# PAGE2.net
KiCad netlist of a schematic drawn in Altium Designer
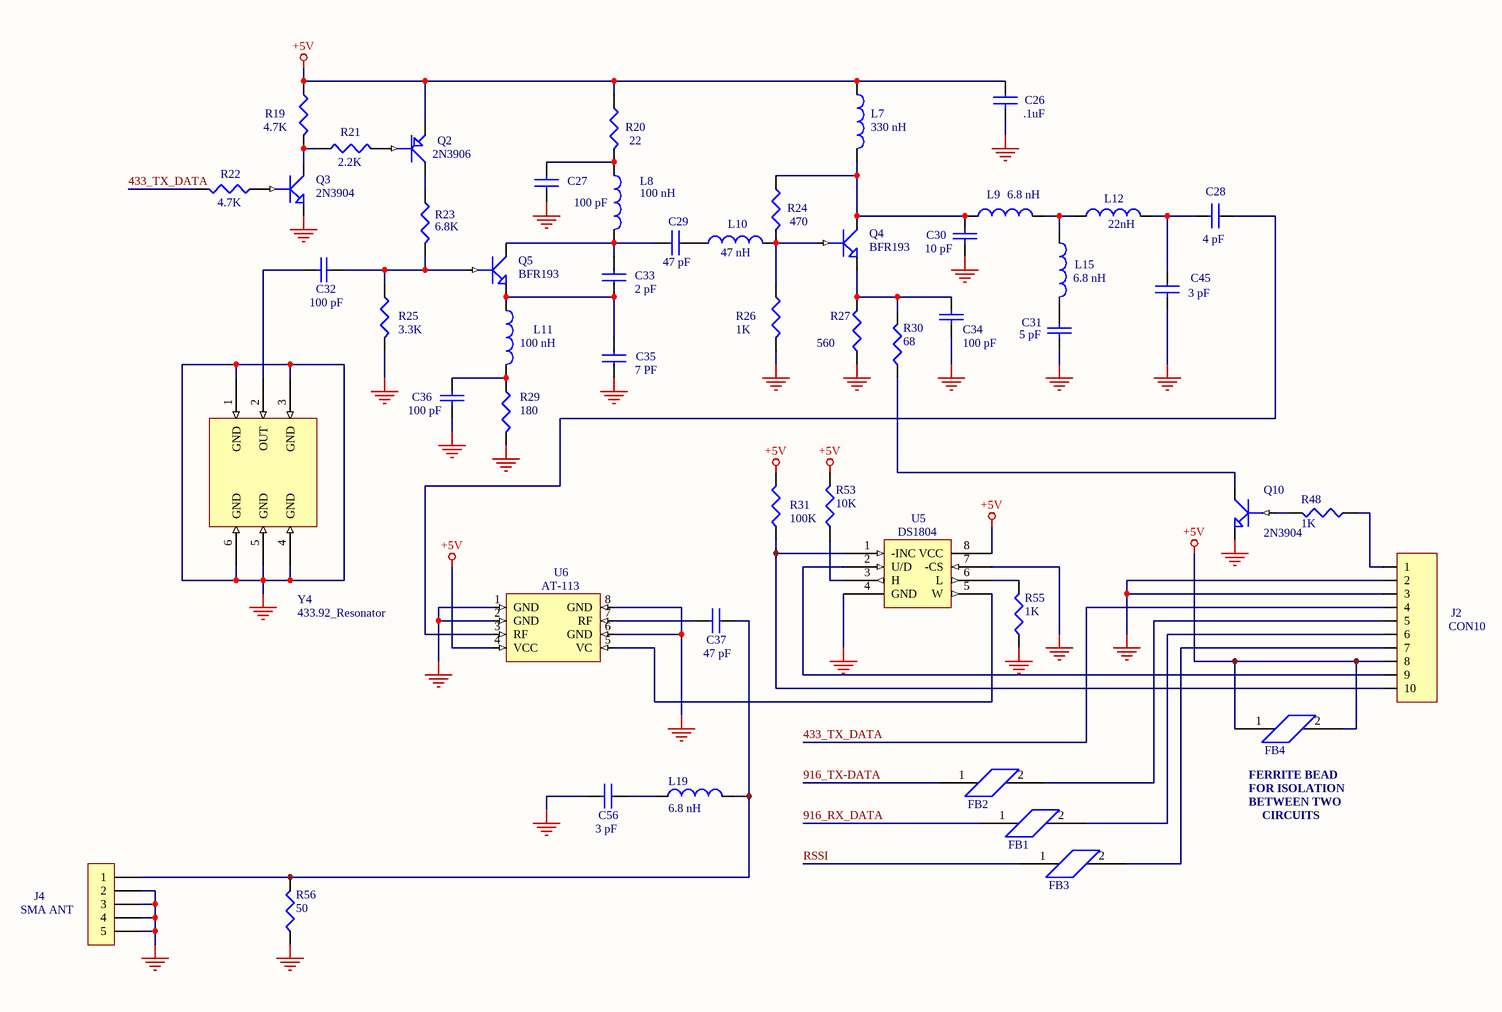
[diagram p0: PAGE2.SCHDOC]

(export (version "E")
  (design (tool "Eeschema 10.0.6"))
  (components
    (comp (ref "C26") (value ".1uF") (footprint "0603") (libsource (lib "*") (part "CAP_NP")))
    (comp (ref "C27") (value "100 pF") (footprint "0603") (libsource (lib "*") (part "CAP_NP")))
    (comp (ref "C28") (value "4 pF") (footprint "0603") (libsource (lib "*") (part "CAP_NP")))
    (comp (ref "C29") (value "47 pF") (footprint "0603") (libsource (lib "*") (part "CAP_NP")))
    (comp (ref "C30")
      (value "10 pF")
      (footprint "0603")
      (description "Capacitor")
      (libsource (lib "*") (part "CAP"))
    )
    (comp (ref "C31")
      (value "5 pF")
      (footprint "0603")
      (description "Capacitor")
      (libsource (lib "*") (part "CAP"))
    )
    (comp (ref "C32")
      (value "100 pF")
      (footprint "0603")
      (description "Capacitor")
      (libsource (lib "*") (part "CAP"))
    )
    (comp (ref "C33") (value "2 pF") (footprint "0603") (libsource (lib "*") (part "CAP_NP")))
    (comp (ref "C34")
      (value "100 pF")
      (footprint "0603")
      (description "Capacitor")
      (libsource (lib "*") (part "CAP"))
    )
    (comp (ref "C35") (value "7 PF") (footprint "0603") (libsource (lib "*") (part "CAP_NP")))
    (comp (ref "C36")
      (value "100 pF")
      (footprint "0603")
      (description "Capacitor")
      (libsource (lib "*") (part "CAP"))
    )
    (comp (ref "C37") (value "47 pF") (footprint "0603") (libsource (lib "*") (part "CAP_NP")))
    (comp (ref "C45") (value "3 pF") (footprint "0603") (libsource (lib "*") (part "CAP_NP")))
    (comp (ref "C56") (value "3 pF") (footprint "0603") (libsource (lib "*") (part "CAP_NP")))
    (comp (ref "FB1") (value "FB") (footprint "0603") (libsource (lib "*") (part "FB_0603")))
    (comp (ref "FB2") (value "FB") (footprint "0603") (libsource (lib "*") (part "FB_0603")))
    (comp (ref "FB3") (value "FB") (footprint "0603") (libsource (lib "*") (part "FB_0603")))
    (comp (ref "FB4") (value "FB") (footprint "0603") (libsource (lib "*") (part "FB_0603")))
    (comp (ref "J2") (value "CON10") (footprint "1X10 HEADER") (libsource (lib "*") (part "CON10")))
    (comp (ref "J4")
      (value "SMA ANT")
      (footprint "50 OHM ANT")
      (description "Connector")
      (libsource (lib "*") (part "CON5"))
    )
    (comp (ref "L7") (value "330 nH") (footprint "0805") (libsource (lib "*") (part "INDUCTOR")))
    (comp (ref "L8") (value "100 nH") (footprint "0603") (libsource (lib "*") (part "INDUCTOR")))
    (comp (ref "L9") (value "6.8 nH") (footprint "0603") (libsource (lib "*") (part "INDUCTOR")))
    (comp (ref "L10") (value "47 nH") (footprint "0603") (libsource (lib "*") (part "INDUCTOR")))
    (comp (ref "L11") (value "100 nH") (footprint "0603") (libsource (lib "*") (part "INDUCTOR")))
    (comp (ref "L12") (value "22nH") (footprint "0603") (libsource (lib "*") (part "INDUCTOR")))
    (comp (ref "L15") (value "6.8 nH") (footprint "0603") (libsource (lib "*") (part "INDUCTOR")))
    (comp (ref "L19") (value "6.8 nH") (footprint "0603") (libsource (lib "*") (part "INDUCTOR")))
    (comp (ref "Q2")
      (value "2N3906")
      (footprint "SOT23 TRANS")
      (description "PNP Transistor")
      (libsource (lib "*") (part "PNP1"))
    )
    (comp (ref "Q3")
      (value "2N3904")
      (footprint "SOT23 TRANS")
      (description "NPN Transistor")
      (libsource (lib "*") (part "NPN1"))
    )
    (comp (ref "Q4")
      (value "BFR193")
      (footprint "SOT23 TRANS")
      (description "NPN Transistor")
      (libsource (lib "*") (part "NPN1"))
    )
    (comp (ref "Q5")
      (value "BFR193")
      (footprint "SOT23 TRANS")
      (description "NPN Transistor")
      (libsource (lib "*") (part "NPN1"))
    )
    (comp (ref "Q10")
      (value "2N3904")
      (footprint "SOT23 TRANS")
      (description "NPN Transistor")
      (libsource (lib "*") (part "NPN1"))
    )
    (comp (ref "R19") (value "4.7K") (footprint "0603") (libsource (lib "*") (part "RESISTOR")))
    (comp (ref "R20") (value "22") (footprint "0603") (libsource (lib "*") (part "RESISTOR")))
    (comp (ref "R21") (value "2.2K") (footprint "0603") (libsource (lib "*") (part "RESISTOR")))
    (comp (ref "R22") (value "4.7K") (footprint "0603") (libsource (lib "*") (part "RESISTOR")))
    (comp (ref "R23") (value "6.8K") (footprint "0603") (libsource (lib "*") (part "RESISTOR")))
    (comp (ref "R24") (value "470") (footprint "0603") (libsource (lib "*") (part "RESISTOR")))
    (comp (ref "R25") (value "3.3K") (footprint "0603") (libsource (lib "*") (part "RESISTOR")))
    (comp (ref "R26") (value "1K") (footprint "0603") (libsource (lib "*") (part "RESISTOR")))
    (comp (ref "R27") (value "560") (footprint "0603") (libsource (lib "*") (part "RESISTOR")))
    (comp (ref "R29") (value "180") (footprint "0603") (libsource (lib "*") (part "RESISTOR")))
    (comp (ref "R30") (value "68") (footprint "0603") (libsource (lib "*") (part "RESISTOR")))
    (comp (ref "R31") (value "100K") (footprint "0603") (libsource (lib "*") (part "RESISTOR")))
    (comp (ref "R48") (value "1K") (footprint "0603") (libsource (lib "*") (part "RESISTOR")))
    (comp (ref "R53") (value "10K") (footprint "0603") (libsource (lib "*") (part "RESISTOR")))
    (comp (ref "R55") (value "1K") (footprint "0603") (libsource (lib "*") (part "RESISTOR")))
    (comp (ref "R56") (value "50") (footprint "0603") (libsource (lib "*") (part "RESISTOR")))
    (comp (ref "U5") (value "DS1804") (footprint "SO8 SMALL") (libsource (lib "*") (part "DS1804")))
    (comp (ref "U6") (value "AT-113") (footprint "SO8") (libsource (lib "*") (part "AT-113A")))
    (comp (ref "Y4")
      (value "433.92_Resonator")
      (footprint "RESONATOR2")
      (libsource (lib "*") (part "RESONATOR2"))
    )
  )
  (nets
    (net (code "1") (name "+5V") (class "Default")
      (node (ref "C26") (pin "1") (pinfunction "1_1") (pintype "passive"))
      (node (ref "FB4") (pin "1") (pinfunction "2_1") (pintype "passive"))
      (node (ref "FB4") (pin "2") (pinfunction "1_2") (pintype "passive"))
      (node (ref "J2") (pin "8") (pinfunction "8_8") (pintype "passive"))
      (node (ref "L7") (pin "1") (pinfunction "1_1") (pintype "passive"))
      (node (ref "Q2") (pin "E") (pinfunction "E_E") (pintype "passive"))
      (node (ref "R19") (pin "1") (pinfunction "1_1") (pintype "passive"))
      (node (ref "R20") (pin "1") (pinfunction "1_1") (pintype "passive"))
      (node (ref "R31") (pin "1") (pinfunction "1_1") (pintype "passive"))
      (node (ref "R53") (pin "2") (pinfunction "2_2") (pintype "passive"))
      (node (ref "U5") (pin "8") (pinfunction "VCC_8") (pintype "power_in"))
      (node (ref "U6") (pin "4") (pinfunction "VCC_4") (pintype "input"))
    )
    (net (code "2") (name "/433_TX_DATA") (class "Default")
      (node (ref "J2") (pin "4") (pinfunction "4_4") (pintype "passive"))
      (node (ref "R22") (pin "2") (pinfunction "2_2") (pintype "passive"))
    )
    (net (code "3") (name "/916_RX_DATA") (class "Default")
      (node (ref "FB1") (pin "1") (pinfunction "2_1") (pintype "passive"))
    )
    (net (code "4") (name "/916_TX-DATA") (class "Default")
      (node (ref "FB2") (pin "1") (pinfunction "2_1") (pintype "passive"))
    )
    (net (code "5") (name "/RSSI") (class "Default")
      (node (ref "FB3") (pin "1") (pinfunction "2_1") (pintype "passive"))
    )
    (net (code "6") (name "GND_SIGNAL") (class "Default")
      (node (ref "C26") (pin "2") (pinfunction "2_2") (pintype "passive"))
      (node (ref "C27") (pin "1") (pinfunction "1_1") (pintype "passive"))
      (node (ref "C30") (pin "2") (pinfunction "2_2") (pintype "passive"))
      (node (ref "C31") (pin "2") (pinfunction "2_2") (pintype "passive"))
      (node (ref "C34") (pin "2") (pinfunction "2_2") (pintype "passive"))
      (node (ref "C35") (pin "1") (pinfunction "1_1") (pintype "passive"))
      (node (ref "C36") (pin "2") (pinfunction "2_2") (pintype "passive"))
      (node (ref "C45") (pin "2") (pinfunction "2_2") (pintype "passive"))
      (node (ref "C56") (pin "2") (pinfunction "2_2") (pintype "passive"))
      (node (ref "J2") (pin "2") (pinfunction "2_2") (pintype "passive"))
      (node (ref "J2") (pin "3") (pinfunction "3_3") (pintype "passive"))
      (node (ref "J4") (pin "2") (pinfunction "2_2") (pintype "passive"))
      (node (ref "J4") (pin "3") (pinfunction "3_3") (pintype "passive"))
      (node (ref "J4") (pin "4") (pinfunction "4_4") (pintype "passive"))
      (node (ref "J4") (pin "5") (pinfunction "5_5") (pintype "passive"))
      (node (ref "Q10") (pin "E") (pinfunction "E_E") (pintype "passive"))
      (node (ref "Q3") (pin "E") (pinfunction "E_E") (pintype "passive"))
      (node (ref "R25") (pin "2") (pinfunction "2_2") (pintype "passive"))
      (node (ref "R26") (pin "2") (pinfunction "2_2") (pintype "passive"))
      (node (ref "R27") (pin "2") (pinfunction "2_2") (pintype "passive"))
      (node (ref "R29") (pin "2") (pinfunction "2_2") (pintype "passive"))
      (node (ref "R55") (pin "1") (pinfunction "1_1") (pintype "passive"))
      (node (ref "R56") (pin "1") (pinfunction "1_1") (pintype "passive"))
      (node (ref "U5") (pin "4") (pinfunction "GND_4") (pintype "power_in"))
      (node (ref "U5") (pin "7") (pinfunction "-CS_7") (pintype "input"))
      (node (ref "U6") (pin "1") (pinfunction "GND_1") (pintype "input"))
      (node (ref "U6") (pin "2") (pinfunction "GND_2") (pintype "input"))
      (node (ref "U6") (pin "6") (pinfunction "GND_6") (pintype "input"))
      (node (ref "U6") (pin "8") (pinfunction "GND_8") (pintype "input"))
      (node (ref "Y4") (pin "1") (pinfunction "GND_1") (pintype "input"))
      (node (ref "Y4") (pin "3") (pinfunction "GND_3") (pintype "input"))
      (node (ref "Y4") (pin "4") (pinfunction "GND_4") (pintype "input"))
      (node (ref "Y4") (pin "5") (pinfunction "GND_5") (pintype "input"))
      (node (ref "Y4") (pin "6") (pinfunction "GND_6") (pintype "input"))
    )
    (net (code "7") (name "Net-(C27-Pad2)") (class "Default")
      (node (ref "C27") (pin "2") (pinfunction "2_2") (pintype "passive"))
      (node (ref "L8") (pin "1") (pinfunction "1_1") (pintype "passive"))
      (node (ref "R20") (pin "2") (pinfunction "2_2") (pintype "passive"))
    )
    (net (code "8") (name "Net-(C28-Pad1)") (class "Default")
      (node (ref "C28") (pin "1") (pinfunction "1_1") (pintype "passive"))
      (node (ref "U6") (pin "3") (pinfunction "RF_3") (pintype "input"))
    )
    (net (code "9") (name "Net-(C28-Pad2)") (class "Default")
      (node (ref "C28") (pin "2") (pinfunction "2_2") (pintype "passive"))
      (node (ref "C45") (pin "1") (pinfunction "1_1") (pintype "passive"))
      (node (ref "L12") (pin "2") (pinfunction "2_2") (pintype "passive"))
    )
    (net (code "10") (name "Net-(C29-Pad1)") (class "Default")
      (node (ref "C29") (pin "1") (pinfunction "1_1") (pintype "passive"))
      (node (ref "L10") (pin "1") (pinfunction "1_1") (pintype "passive"))
    )
    (net (code "11") (name "Net-(C29-Pad2)") (class "Default")
      (node (ref "C29") (pin "2") (pinfunction "2_2") (pintype "passive"))
      (node (ref "C33") (pin "2") (pinfunction "2_2") (pintype "passive"))
      (node (ref "L8") (pin "2") (pinfunction "2_2") (pintype "passive"))
      (node (ref "Q5") (pin "C") (pinfunction "C_C") (pintype "passive"))
    )
    (net (code "12") (name "Net-(C30-Pad1)") (class "Default")
      (node (ref "C30") (pin "1") (pinfunction "1_1") (pintype "passive"))
      (node (ref "L7") (pin "2") (pinfunction "2_2") (pintype "passive"))
      (node (ref "L9") (pin "1") (pinfunction "1_1") (pintype "passive"))
      (node (ref "Q4") (pin "C") (pinfunction "C_C") (pintype "passive"))
      (node (ref "R24") (pin "1") (pinfunction "1_1") (pintype "passive"))
    )
    (net (code "13") (name "Net-(C31-Pad1)") (class "Default")
      (node (ref "C31") (pin "1") (pinfunction "1_1") (pintype "passive"))
      (node (ref "L15") (pin "2") (pinfunction "2_2") (pintype "passive"))
    )
    (net (code "14") (name "Net-(C32-Pad2)") (class "Default")
      (node (ref "C32") (pin "2") (pinfunction "2_2") (pintype "passive"))
      (node (ref "Q5") (pin "B") (pinfunction "B_B") (pintype "input"))
      (node (ref "R23") (pin "2") (pinfunction "2_2") (pintype "passive"))
      (node (ref "R25") (pin "1") (pinfunction "1_1") (pintype "passive"))
    )
    (net (code "15") (name "Net-(C33-Pad1)") (class "Default")
      (node (ref "C33") (pin "1") (pinfunction "1_1") (pintype "passive"))
      (node (ref "C35") (pin "2") (pinfunction "2_2") (pintype "passive"))
      (node (ref "L11") (pin "1") (pinfunction "1_1") (pintype "passive"))
      (node (ref "Q5") (pin "E") (pinfunction "E_E") (pintype "passive"))
    )
    (net (code "16") (name "Net-(C34-Pad1)") (class "Default")
      (node (ref "C34") (pin "1") (pinfunction "1_1") (pintype "passive"))
      (node (ref "Q4") (pin "E") (pinfunction "E_E") (pintype "passive"))
      (node (ref "R27") (pin "1") (pinfunction "1_1") (pintype "passive"))
      (node (ref "R30") (pin "2") (pinfunction "2_2") (pintype "passive"))
    )
    (net (code "17") (name "Net-(C36-Pad1)") (class "Default")
      (node (ref "C36") (pin "1") (pinfunction "1_1") (pintype "passive"))
      (node (ref "L11") (pin "2") (pinfunction "2_2") (pintype "passive"))
      (node (ref "R29") (pin "1") (pinfunction "1_1") (pintype "passive"))
    )
    (net (code "18") (name "Net-(C37-Pad1)") (class "Default")
      (node (ref "C37") (pin "1") (pinfunction "1_1") (pintype "passive"))
      (node (ref "J4") (pin "1") (pinfunction "1_1") (pintype "passive"))
      (node (ref "L19") (pin "2") (pinfunction "2_2") (pintype "passive"))
      (node (ref "R56") (pin "2") (pinfunction "2_2") (pintype "passive"))
    )
    (net (code "19") (name "Net-(C37-Pad2)") (class "Default")
      (node (ref "C37") (pin "2") (pinfunction "2_2") (pintype "passive"))
      (node (ref "U6") (pin "7") (pinfunction "RF_7") (pintype "input"))
    )
    (net (code "20") (name "Net-(C56-Pad1)") (class "Default")
      (node (ref "C56") (pin "1") (pinfunction "1_1") (pintype "passive"))
      (node (ref "L19") (pin "1") (pinfunction "1_1") (pintype "passive"))
    )
    (net (code "21") (name "Net-(FB1-1)") (class "Default")
      (node (ref "FB1") (pin "2") (pinfunction "1_2") (pintype "passive"))
      (node (ref "J2") (pin "6") (pinfunction "6_6") (pintype "passive"))
    )
    (net (code "22") (name "Net-(FB2-1)") (class "Default")
      (node (ref "FB2") (pin "2") (pinfunction "1_2") (pintype "passive"))
      (node (ref "J2") (pin "5") (pinfunction "5_5") (pintype "passive"))
    )
    (net (code "23") (name "Net-(FB3-1)") (class "Default")
      (node (ref "FB3") (pin "2") (pinfunction "1_2") (pintype "passive"))
      (node (ref "J2") (pin "7") (pinfunction "7_7") (pintype "passive"))
    )
    (net (code "24") (name "Net-(J2-Pad1)") (class "Default")
      (node (ref "J2") (pin "1") (pinfunction "1_1") (pintype "passive"))
      (node (ref "R48") (pin "2") (pinfunction "2_2") (pintype "passive"))
    )
    (net (code "25") (name "Net-(L10-Pad2)") (class "Default")
      (node (ref "L10") (pin "2") (pinfunction "2_2") (pintype "passive"))
      (node (ref "Q4") (pin "B") (pinfunction "B_B") (pintype "input"))
      (node (ref "R24") (pin "2") (pinfunction "2_2") (pintype "passive"))
      (node (ref "R26") (pin "1") (pinfunction "1_1") (pintype "passive"))
    )
    (net (code "26") (name "Net-(L12-Pad1)") (class "Default")
      (node (ref "L12") (pin "1") (pinfunction "1_1") (pintype "passive"))
      (node (ref "L15") (pin "1") (pinfunction "1_1") (pintype "passive"))
      (node (ref "L9") (pin "2") (pinfunction "2_2") (pintype "passive"))
    )
    (net (code "27") (name "Net-(Q2-PadB)") (class "Default")
      (node (ref "Q2") (pin "B") (pinfunction "B_B") (pintype "input"))
      (node (ref "R21") (pin "2") (pinfunction "2_2") (pintype "passive"))
    )
    (net (code "28") (name "Net-(Q2-PadC)") (class "Default")
      (node (ref "Q2") (pin "C") (pinfunction "C_C") (pintype "passive"))
      (node (ref "R23") (pin "1") (pinfunction "1_1") (pintype "passive"))
    )
    (net (code "29") (name "Net-(Q3-PadB)") (class "Default")
      (node (ref "Q3") (pin "B") (pinfunction "B_B") (pintype "input"))
      (node (ref "R22") (pin "1") (pinfunction "1_1") (pintype "passive"))
    )
    (net (code "30") (name "Net-(Q3-PadC)") (class "Default")
      (node (ref "Q3") (pin "C") (pinfunction "C_C") (pintype "passive"))
      (node (ref "R19") (pin "2") (pinfunction "2_2") (pintype "passive"))
      (node (ref "R21") (pin "1") (pinfunction "1_1") (pintype "passive"))
    )
    (net (code "31") (name "Net-(Q10-PadB)") (class "Default")
      (node (ref "Q10") (pin "B") (pinfunction "B_B") (pintype "input"))
      (node (ref "R48") (pin "1") (pinfunction "1_1") (pintype "passive"))
    )
    (net (code "32") (name "Net-(Q10-PadC)") (class "Default")
      (node (ref "Q10") (pin "C") (pinfunction "C_C") (pintype "passive"))
      (node (ref "R30") (pin "1") (pinfunction "1_1") (pintype "passive"))
    )
    (net (code "33") (name "Net-(U5--INC)") (class "Default")
      (node (ref "J2") (pin "10") (pinfunction "10_10") (pintype "passive"))
      (node (ref "R31") (pin "2") (pinfunction "2_2") (pintype "passive"))
      (node (ref "U5") (pin "1") (pinfunction "-INC_1") (pintype "input"))
    )
    (net (code "34") (name "Net-(U5-H)") (class "Default")
      (node (ref "R53") (pin "1") (pinfunction "1_1") (pintype "passive"))
      (node (ref "U5") (pin "3") (pinfunction "H_3") (pintype "output"))
    )
    (net (code "35") (name "Net-(U5-L)") (class "Default")
      (node (ref "R55") (pin "2") (pinfunction "2_2") (pintype "passive"))
      (node (ref "U5") (pin "6") (pinfunction "L_6") (pintype "output"))
    )
    (net (code "36") (name "Net-(U5-U{slash}D)") (class "Default")
      (node (ref "J2") (pin "9") (pinfunction "9_9") (pintype "passive"))
      (node (ref "U5") (pin "2") (pinfunction "U/D_2") (pintype "input"))
    )
    (net (code "37") (name "Net-(U5-W)") (class "Default")
      (node (ref "U5") (pin "5") (pinfunction "W_5") (pintype "output"))
      (node (ref "U6") (pin "5") (pinfunction "VC_5") (pintype "input"))
    )
    (net (code "38") (name "Net-(Y4-OUT)") (class "Default")
      (node (ref "C32") (pin "1") (pinfunction "1_1") (pintype "passive"))
      (node (ref "Y4") (pin "2") (pinfunction "OUT_2") (pintype "input"))
    )
  )
)
